# Desertlure.net
KiCad netlist of a schematic drawn in EAGLE
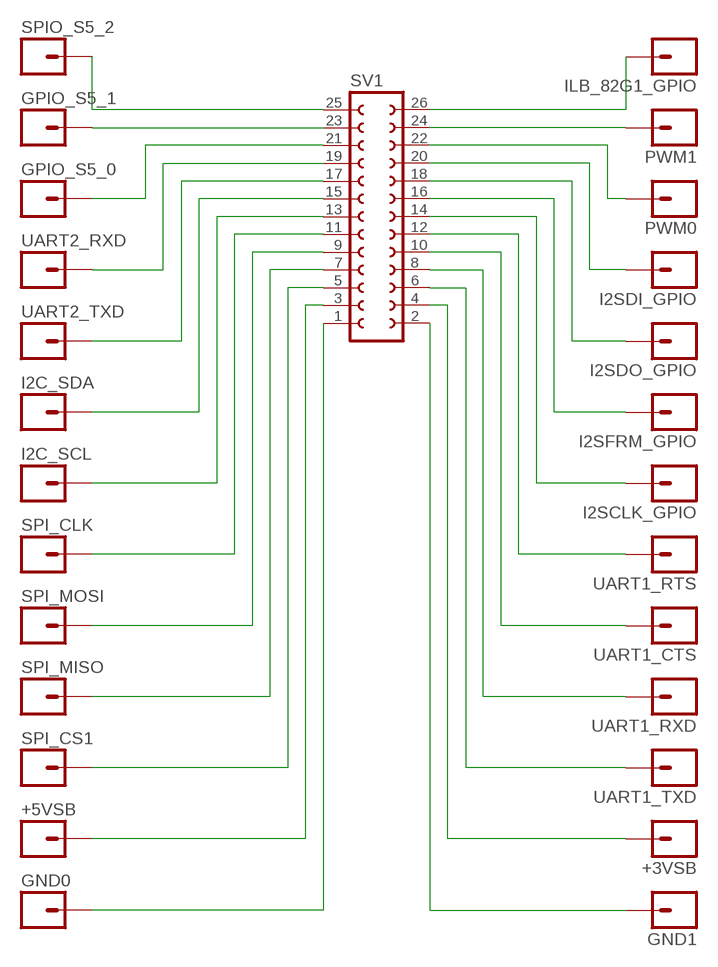
[diagram p0: schematic, sheet 1]

(export (version "E")
  (design (tool "Eeschema 10.0.6"))
  (components
    (comp (ref "+3VSB")
      (value "M01NOSILK-KIT")
      (footprint "eagle-import:1X01NS-KIT")
      (libsource (lib "eagle-import") (part "M01NOSILK-KIT"))
    )
    (comp (ref "+5VSB")
      (value "M01NOSILK-KIT")
      (footprint "eagle-import:1X01NS-KIT")
      (libsource (lib "eagle-import") (part "M01NOSILK-KIT"))
    )
    (comp (ref "GND0")
      (value "M01NOSILK-KIT")
      (footprint "eagle-import:1X01NS-KIT")
      (libsource (lib "eagle-import") (part "M01NOSILK-KIT"))
    )
    (comp (ref "GND1")
      (value "M01NOSILK-KIT")
      (footprint "eagle-import:1X01NS-KIT")
      (libsource (lib "eagle-import") (part "M01NOSILK-KIT"))
    )
    (comp (ref "GPIO_S5_0")
      (value "M01NOSILK-KIT")
      (footprint "eagle-import:1X01NS-KIT")
      (libsource (lib "eagle-import") (part "M01NOSILK-KIT"))
    )
    (comp (ref "GPIO_S5_1")
      (value "M01NOSILK-KIT")
      (footprint "eagle-import:1X01NS-KIT")
      (libsource (lib "eagle-import") (part "M01NOSILK-KIT"))
    )
    (comp (ref "I2C_SCL")
      (value "M01NOSILK-KIT")
      (footprint "eagle-import:1X01NS-KIT")
      (libsource (lib "eagle-import") (part "M01NOSILK-KIT"))
    )
    (comp (ref "I2C_SDA")
      (value "M01NOSILK-KIT")
      (footprint "eagle-import:1X01NS-KIT")
      (libsource (lib "eagle-import") (part "M01NOSILK-KIT"))
    )
    (comp (ref "I2SCLK_GPIO")
      (value "M01NOSILK-KIT")
      (footprint "eagle-import:1X01NS-KIT")
      (libsource (lib "eagle-import") (part "M01NOSILK-KIT"))
    )
    (comp (ref "I2SDI_GPIO")
      (value "M01NOSILK-KIT")
      (footprint "eagle-import:1X01NS-KIT")
      (libsource (lib "eagle-import") (part "M01NOSILK-KIT"))
    )
    (comp (ref "I2SDO_GPIO")
      (value "M01NOSILK-KIT")
      (footprint "eagle-import:1X01NS-KIT")
      (libsource (lib "eagle-import") (part "M01NOSILK-KIT"))
    )
    (comp (ref "I2SFRM_GPIO")
      (value "M01NOSILK-KIT")
      (footprint "eagle-import:1X01NS-KIT")
      (libsource (lib "eagle-import") (part "M01NOSILK-KIT"))
    )
    (comp (ref "ILB_82G1_GPIO")
      (value "M01NOSILK-KIT")
      (footprint "eagle-import:1X01NS-KIT")
      (libsource (lib "eagle-import") (part "M01NOSILK-KIT"))
    )
    (comp (ref "PWM0")
      (value "M01NOSILK-KIT")
      (footprint "eagle-import:1X01NS-KIT")
      (libsource (lib "eagle-import") (part "M01NOSILK-KIT"))
    )
    (comp (ref "PWM1")
      (value "M01NOSILK-KIT")
      (footprint "eagle-import:1X01NS-KIT")
      (libsource (lib "eagle-import") (part "M01NOSILK-KIT"))
    )
    (comp (ref "SPIO_S5_2")
      (value "M01NOSILK-KIT")
      (footprint "eagle-import:1X01NS-KIT")
      (libsource (lib "eagle-import") (part "M01NOSILK-KIT"))
    )
    (comp (ref "SPI_CLK")
      (value "M01NOSILK-KIT")
      (footprint "eagle-import:1X01NS-KIT")
      (libsource (lib "eagle-import") (part "M01NOSILK-KIT"))
    )
    (comp (ref "SPI_CS1")
      (value "M01NOSILK-KIT")
      (footprint "eagle-import:1X01NS-KIT")
      (libsource (lib "eagle-import") (part "M01NOSILK-KIT"))
    )
    (comp (ref "SPI_MISO")
      (value "M01NOSILK-KIT")
      (footprint "eagle-import:1X01NS-KIT")
      (libsource (lib "eagle-import") (part "M01NOSILK-KIT"))
    )
    (comp (ref "SPI_MOSI")
      (value "M01NOSILK-KIT")
      (footprint "eagle-import:1X01NS-KIT")
      (libsource (lib "eagle-import") (part "M01NOSILK-KIT"))
    )
    (comp (ref "SV1")
      (value "FE13-2W")
      (footprint "eagle-import:FE13-2W")
      (libsource (lib "eagle-import") (part "FE13-2W"))
    )
    (comp (ref "UART1_CTS")
      (value "M01NOSILK-KIT")
      (footprint "eagle-import:1X01NS-KIT")
      (libsource (lib "eagle-import") (part "M01NOSILK-KIT"))
    )
    (comp (ref "UART1_RTS")
      (value "M01NOSILK-KIT")
      (footprint "eagle-import:1X01NS-KIT")
      (libsource (lib "eagle-import") (part "M01NOSILK-KIT"))
    )
    (comp (ref "UART1_RXD")
      (value "M01NOSILK-KIT")
      (footprint "eagle-import:1X01NS-KIT")
      (libsource (lib "eagle-import") (part "M01NOSILK-KIT"))
    )
    (comp (ref "UART1_TXD")
      (value "M01NOSILK-KIT")
      (footprint "eagle-import:1X01NS-KIT")
      (libsource (lib "eagle-import") (part "M01NOSILK-KIT"))
    )
    (comp (ref "UART2_RXD")
      (value "M01NOSILK-KIT")
      (footprint "eagle-import:1X01NS-KIT")
      (libsource (lib "eagle-import") (part "M01NOSILK-KIT"))
    )
    (comp (ref "UART2_TXD")
      (value "M01NOSILK-KIT")
      (footprint "eagle-import:1X01NS-KIT")
      (libsource (lib "eagle-import") (part "M01NOSILK-KIT"))
    )
  )
  (nets
    (net (code "1") (name "Net-(+3VSB-Pad1)") (class "Default")
      (node (ref "+3VSB") (pin "1") (pinfunction "1_1") (pintype "passive"))
      (node (ref "SV1") (pin "4") (pinfunction "4_4") (pintype "passive"))
    )
    (net (code "2") (name "Net-(+5VSB-Pad1)") (class "Default")
      (node (ref "+5VSB") (pin "1") (pinfunction "1_1") (pintype "passive"))
      (node (ref "SV1") (pin "3") (pinfunction "3_3") (pintype "passive"))
    )
    (net (code "3") (name "Net-(GND0-Pad1)") (class "Default")
      (node (ref "GND0") (pin "1") (pinfunction "1_1") (pintype "passive"))
      (node (ref "SV1") (pin "1") (pinfunction "1_1") (pintype "passive"))
    )
    (net (code "4") (name "Net-(GND1-Pad1)") (class "Default")
      (node (ref "GND1") (pin "1") (pinfunction "1_1") (pintype "passive"))
      (node (ref "SV1") (pin "2") (pinfunction "2_2") (pintype "passive"))
    )
    (net (code "5") (name "Net-(GPIO_S5_0-Pad1)") (class "Default")
      (node (ref "GPIO_S5_0") (pin "1") (pinfunction "1_1") (pintype "passive"))
      (node (ref "SV1") (pin "21") (pinfunction "21_21") (pintype "passive"))
    )
    (net (code "6") (name "Net-(GPIO_S5_1-Pad1)") (class "Default")
      (node (ref "GPIO_S5_1") (pin "1") (pinfunction "1_1") (pintype "passive"))
      (node (ref "SV1") (pin "23") (pinfunction "23_23") (pintype "passive"))
    )
    (net (code "7") (name "Net-(I2C_SCL-Pad1)") (class "Default")
      (node (ref "I2C_SCL") (pin "1") (pinfunction "1_1") (pintype "passive"))
      (node (ref "SV1") (pin "13") (pinfunction "13_13") (pintype "passive"))
    )
    (net (code "8") (name "Net-(I2C_SDA-Pad1)") (class "Default")
      (node (ref "I2C_SDA") (pin "1") (pinfunction "1_1") (pintype "passive"))
      (node (ref "SV1") (pin "15") (pinfunction "15_15") (pintype "passive"))
    )
    (net (code "9") (name "Net-(I2SCLK_GPIO-Pad1)") (class "Default")
      (node (ref "I2SCLK_GPIO") (pin "1") (pinfunction "1_1") (pintype "passive"))
      (node (ref "SV1") (pin "14") (pinfunction "14_14") (pintype "passive"))
    )
    (net (code "10") (name "Net-(I2SDI_GPIO-Pad1)") (class "Default")
      (node (ref "I2SDI_GPIO") (pin "1") (pinfunction "1_1") (pintype "passive"))
      (node (ref "SV1") (pin "20") (pinfunction "20_20") (pintype "passive"))
    )
    (net (code "11") (name "Net-(I2SDO_GPIO-Pad1)") (class "Default")
      (node (ref "I2SDO_GPIO") (pin "1") (pinfunction "1_1") (pintype "passive"))
      (node (ref "SV1") (pin "18") (pinfunction "18_18") (pintype "passive"))
    )
    (net (code "12") (name "Net-(I2SFRM_GPIO-Pad1)") (class "Default")
      (node (ref "I2SFRM_GPIO") (pin "1") (pinfunction "1_1") (pintype "passive"))
      (node (ref "SV1") (pin "16") (pinfunction "16_16") (pintype "passive"))
    )
    (net (code "13") (name "Net-(ILB_82G1_GPIO-Pad1)") (class "Default")
      (node (ref "ILB_82G1_GPIO") (pin "1") (pinfunction "1_1") (pintype "passive"))
      (node (ref "SV1") (pin "26") (pinfunction "26_26") (pintype "passive"))
    )
    (net (code "14") (name "Net-(PWM0-Pad1)") (class "Default")
      (node (ref "PWM0") (pin "1") (pinfunction "1_1") (pintype "passive"))
      (node (ref "SV1") (pin "22") (pinfunction "22_22") (pintype "passive"))
    )
    (net (code "15") (name "Net-(PWM1-Pad1)") (class "Default")
      (node (ref "PWM1") (pin "1") (pinfunction "1_1") (pintype "passive"))
      (node (ref "SV1") (pin "24") (pinfunction "24_24") (pintype "passive"))
    )
    (net (code "16") (name "Net-(SPIO_S5_2-Pad1)") (class "Default")
      (node (ref "SPIO_S5_2") (pin "1") (pinfunction "1_1") (pintype "passive"))
      (node (ref "SV1") (pin "25") (pinfunction "25_25") (pintype "passive"))
    )
    (net (code "17") (name "Net-(SPI_CLK-Pad1)") (class "Default")
      (node (ref "SPI_CLK") (pin "1") (pinfunction "1_1") (pintype "passive"))
      (node (ref "SV1") (pin "11") (pinfunction "11_11") (pintype "passive"))
    )
    (net (code "18") (name "Net-(SPI_CS1-Pad1)") (class "Default")
      (node (ref "SPI_CS1") (pin "1") (pinfunction "1_1") (pintype "passive"))
      (node (ref "SV1") (pin "5") (pinfunction "5_5") (pintype "passive"))
    )
    (net (code "19") (name "Net-(SPI_MISO-Pad1)") (class "Default")
      (node (ref "SPI_MISO") (pin "1") (pinfunction "1_1") (pintype "passive"))
      (node (ref "SV1") (pin "7") (pinfunction "7_7") (pintype "passive"))
    )
    (net (code "20") (name "Net-(SPI_MOSI-Pad1)") (class "Default")
      (node (ref "SPI_MOSI") (pin "1") (pinfunction "1_1") (pintype "passive"))
      (node (ref "SV1") (pin "9") (pinfunction "9_9") (pintype "passive"))
    )
    (net (code "21") (name "Net-(SV1-Pad6)") (class "Default")
      (node (ref "SV1") (pin "6") (pinfunction "6_6") (pintype "passive"))
      (node (ref "UART1_TXD") (pin "1") (pinfunction "1_1") (pintype "passive"))
    )
    (net (code "22") (name "Net-(SV1-Pad8)") (class "Default")
      (node (ref "SV1") (pin "8") (pinfunction "8_8") (pintype "passive"))
      (node (ref "UART1_RXD") (pin "1") (pinfunction "1_1") (pintype "passive"))
    )
    (net (code "23") (name "Net-(SV1-Pad10)") (class "Default")
      (node (ref "SV1") (pin "10") (pinfunction "10_10") (pintype "passive"))
      (node (ref "UART1_CTS") (pin "1") (pinfunction "1_1") (pintype "passive"))
    )
    (net (code "24") (name "Net-(SV1-Pad12)") (class "Default")
      (node (ref "SV1") (pin "12") (pinfunction "12_12") (pintype "passive"))
      (node (ref "UART1_RTS") (pin "1") (pinfunction "1_1") (pintype "passive"))
    )
    (net (code "25") (name "Net-(SV1-Pad17)") (class "Default")
      (node (ref "SV1") (pin "17") (pinfunction "17_17") (pintype "passive"))
      (node (ref "UART2_TXD") (pin "1") (pinfunction "1_1") (pintype "passive"))
    )
    (net (code "26") (name "Net-(SV1-Pad19)") (class "Default")
      (node (ref "SV1") (pin "19") (pinfunction "19_19") (pintype "passive"))
      (node (ref "UART2_RXD") (pin "1") (pinfunction "1_1") (pintype "passive"))
    )
  )
)
